# ProDoc_PT2470.net
KiCad netlist of a schematic drawn in EasyEDA Pro
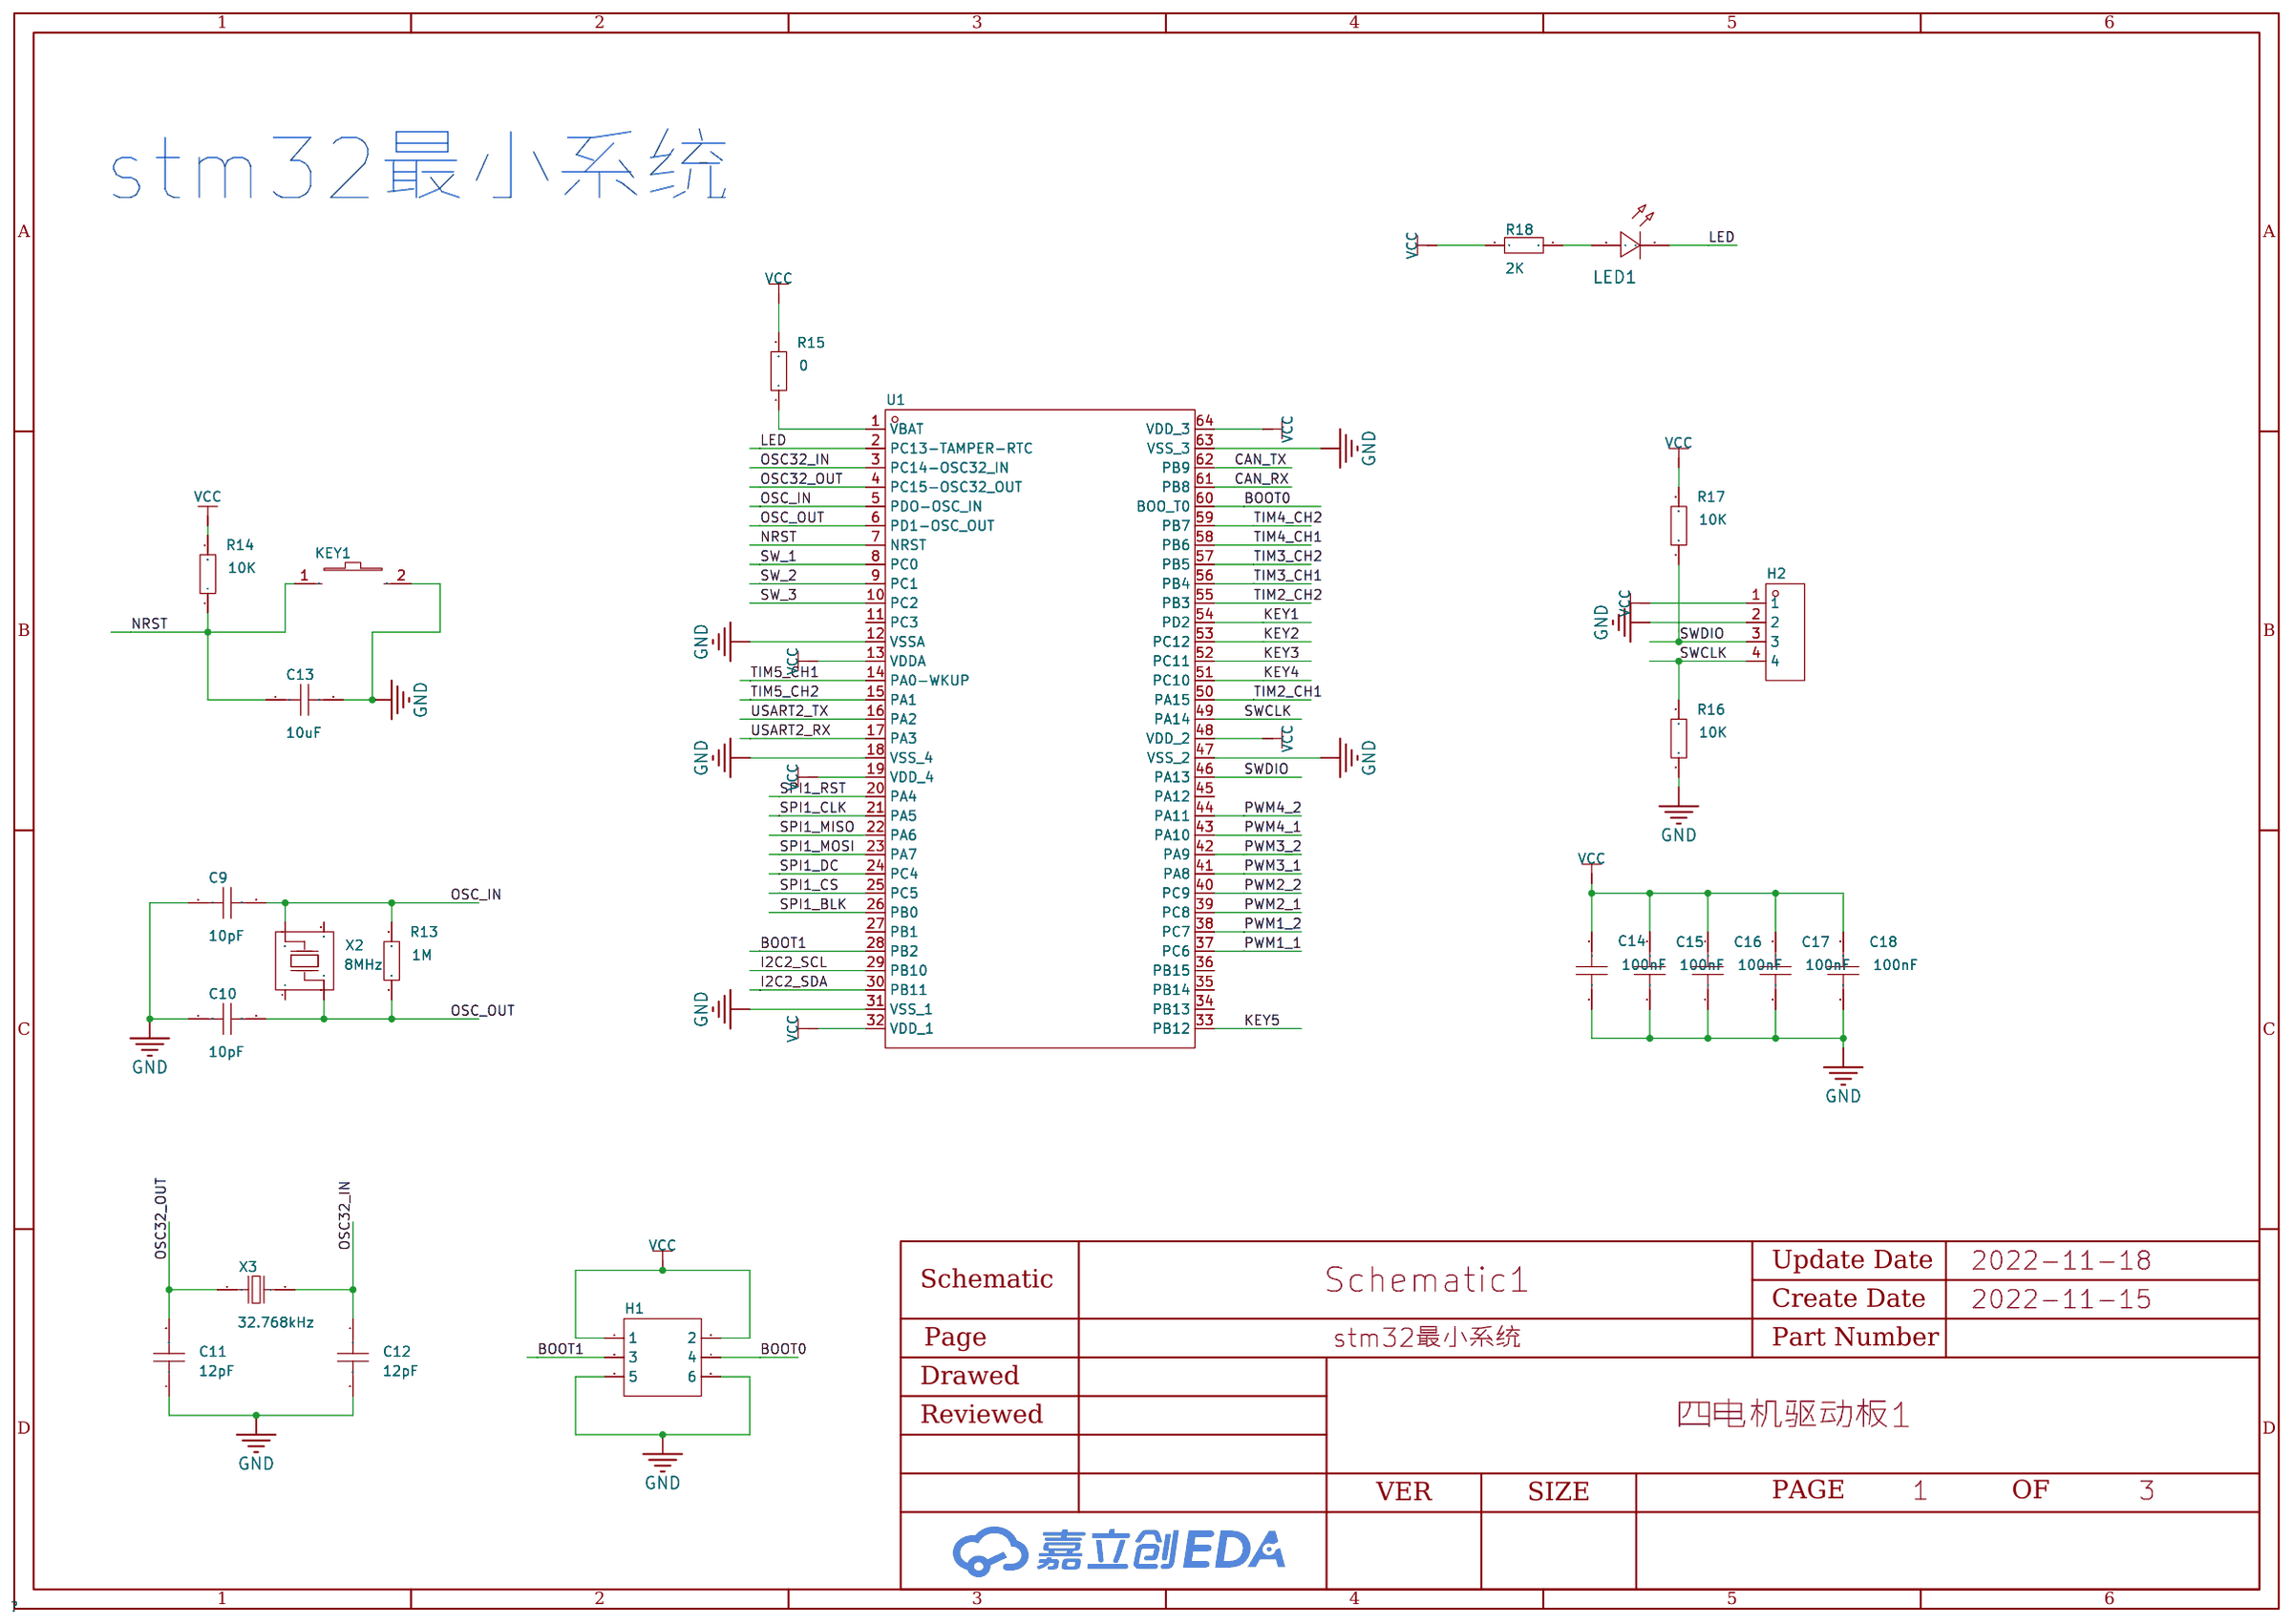
[diagram p0: stm32最小系统]
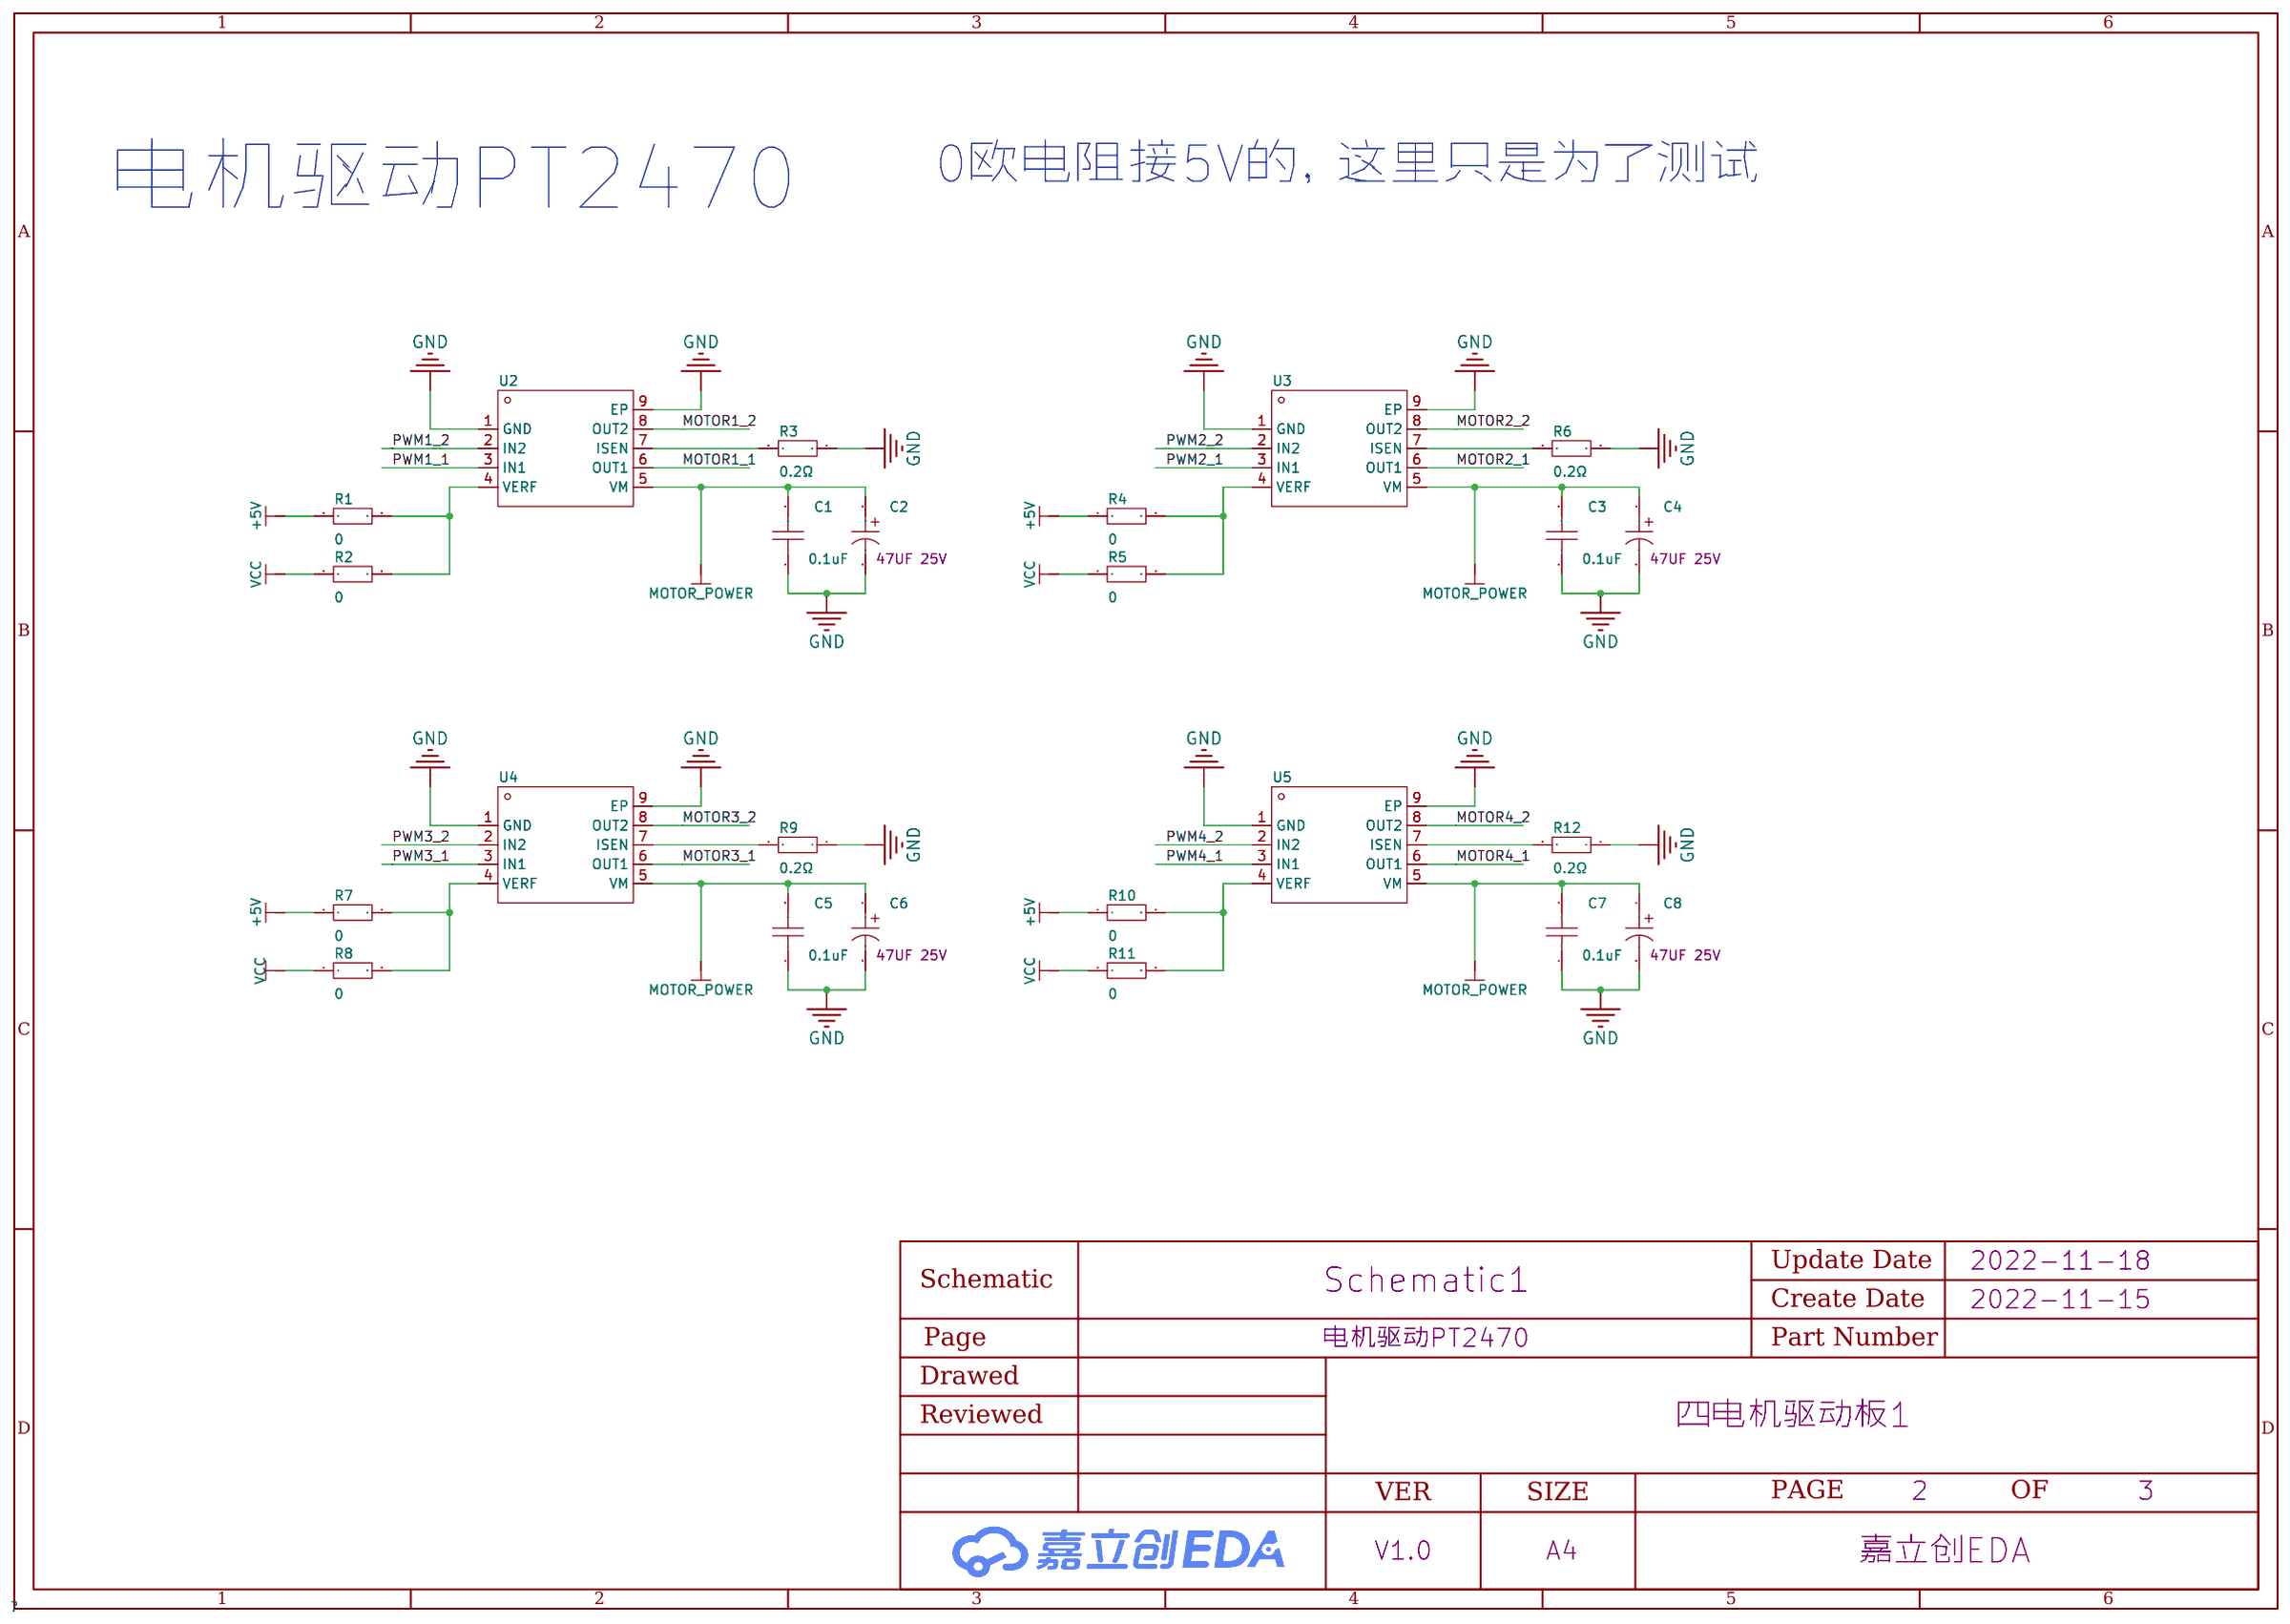
[diagram p1: 电机驱动PT2470]
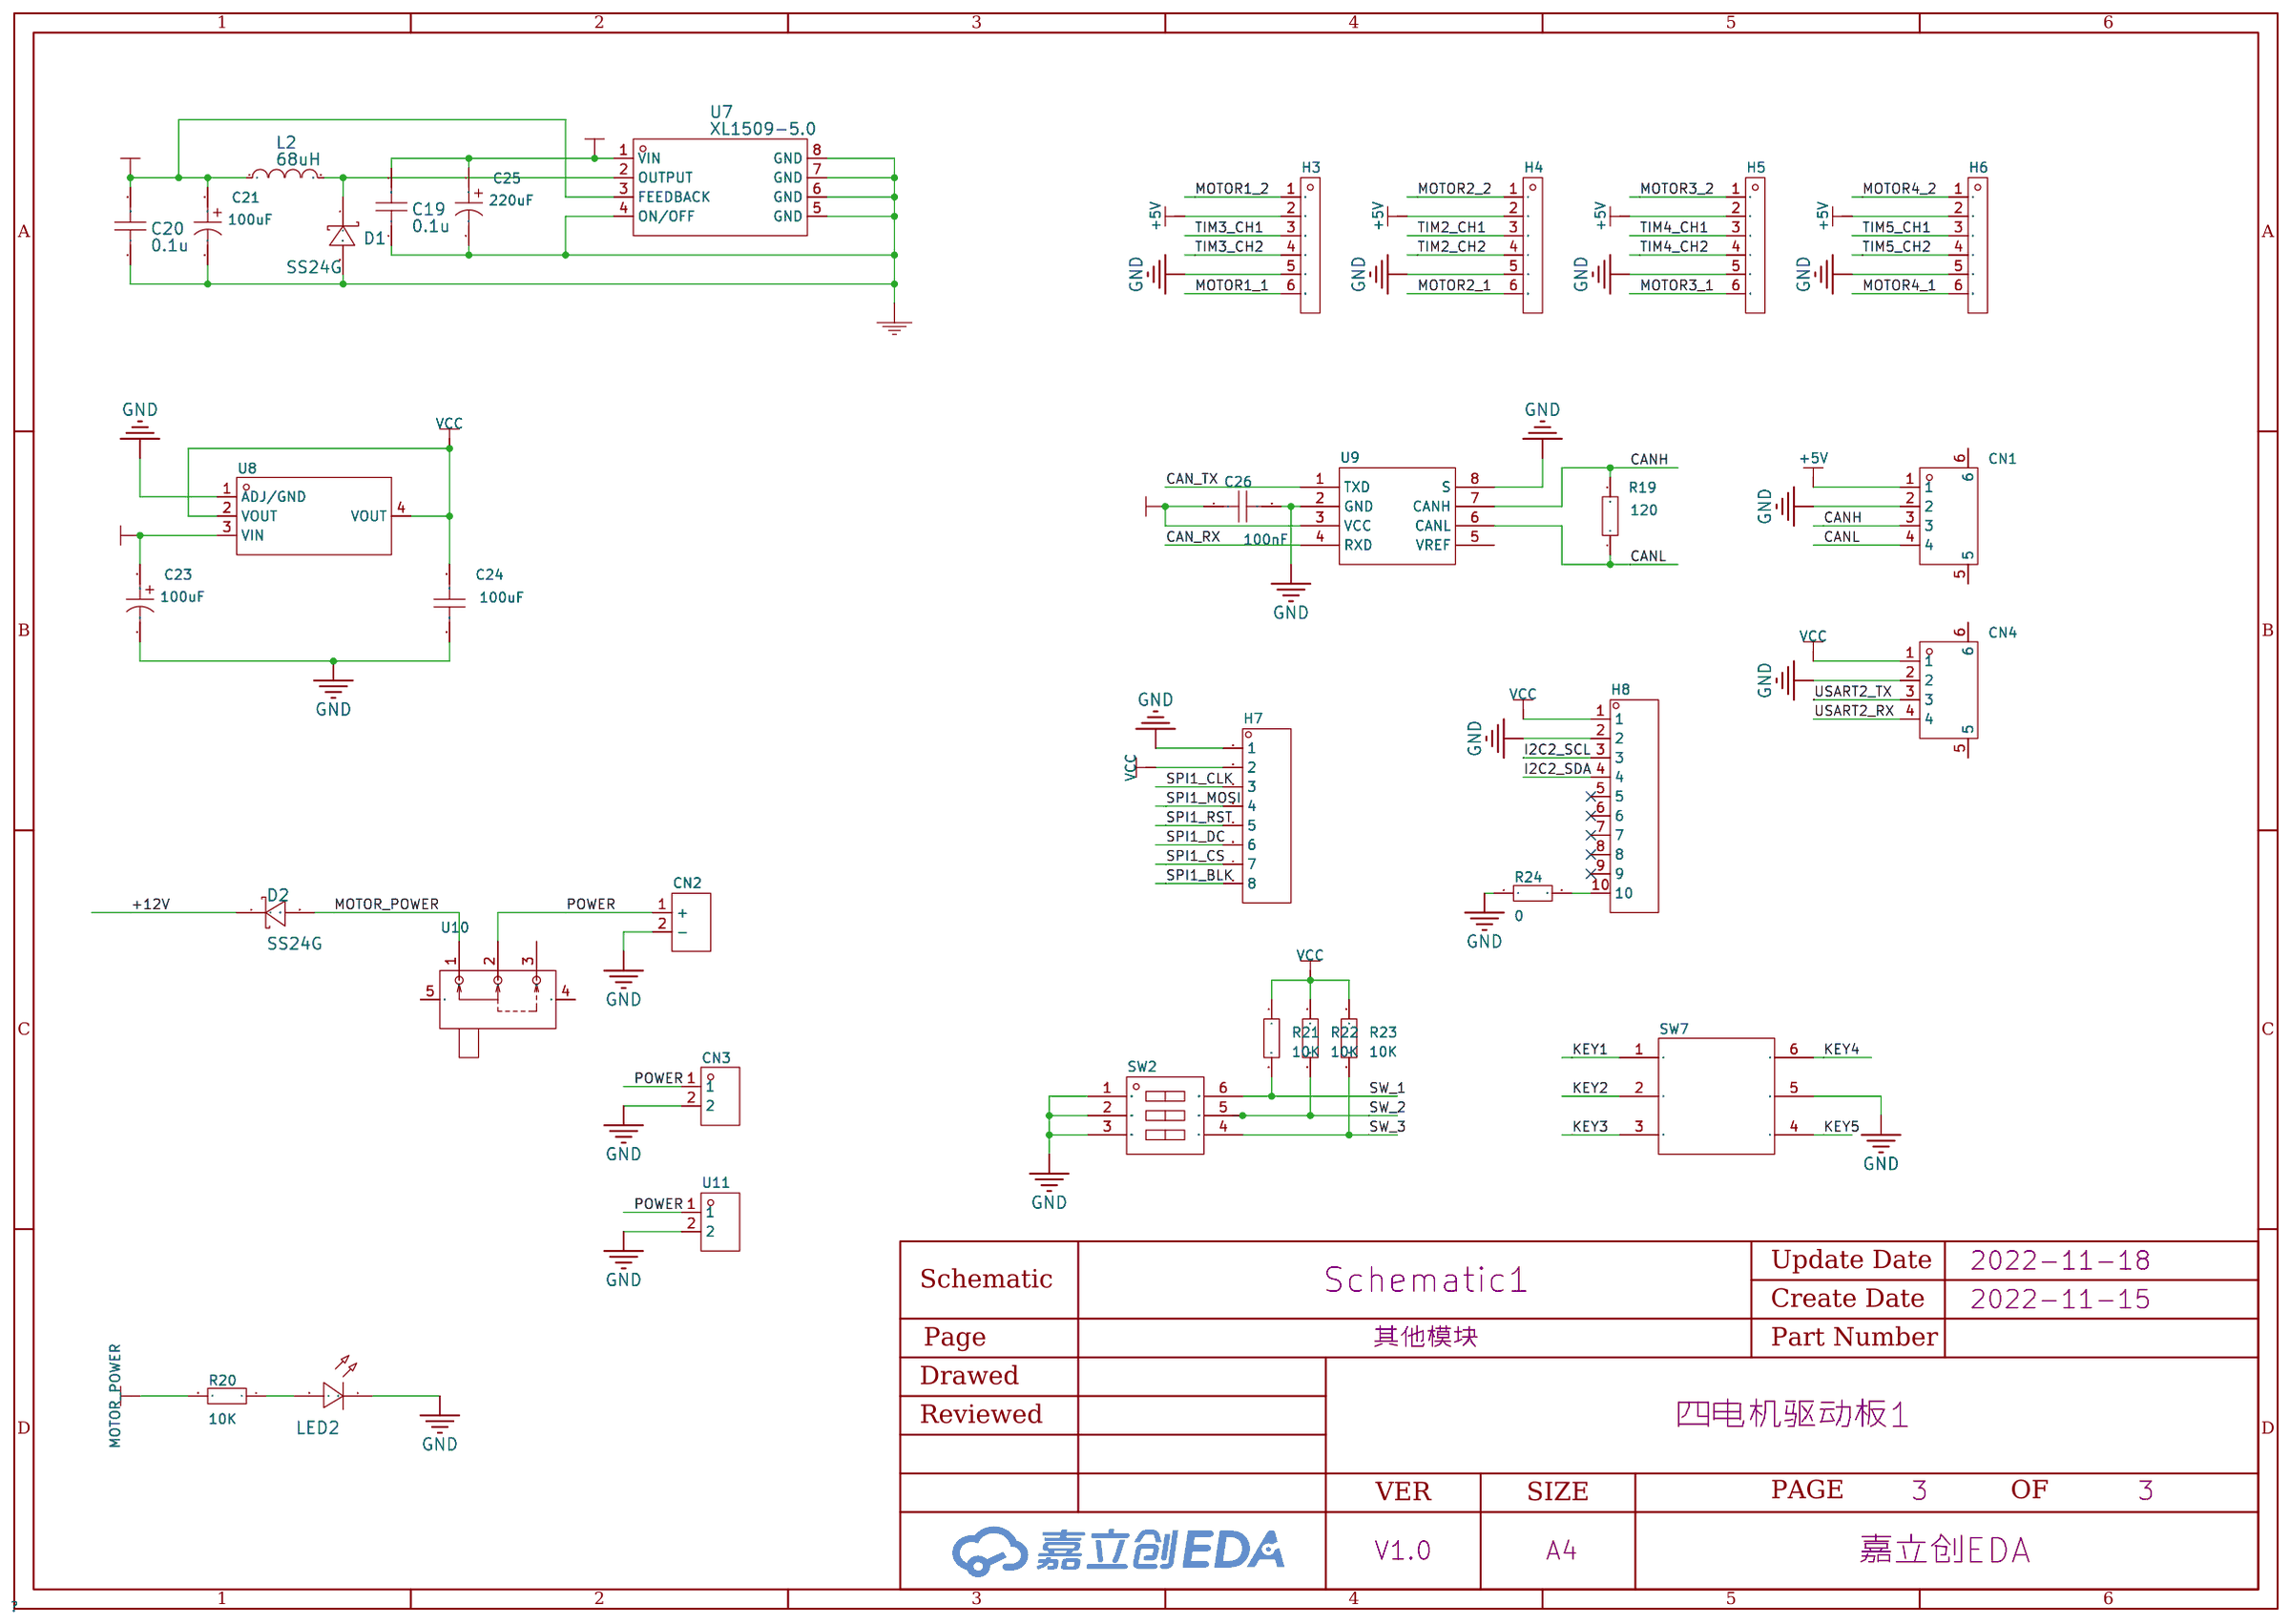
[diagram p2: 其他模块]

(export (version "E")
  (design (tool "Eeschema 10.0.6"))
  (components
    (comp (ref "C9")
      (value "10pF")
      (footprint "easyedapro:C0603")
      (libsource (lib "easyedapro") (part "C1210X7R475K630NT"))
    )
    (comp (ref "C10")
      (value "10pF")
      (footprint "easyedapro:C0603")
      (libsource (lib "easyedapro") (part "C1210X7R475K630NT"))
    )
    (comp (ref "C11")
      (value "12pF")
      (footprint "easyedapro:C0603")
      (libsource (lib "easyedapro") (part "C1210X7R475K630NT"))
    )
    (comp (ref "C12")
      (value "12pF")
      (footprint "easyedapro:C0603")
      (libsource (lib "easyedapro") (part "C1210X7R475K630NT"))
    )
    (comp (ref "C13")
      (value "10uF")
      (footprint "easyedapro:C0603")
      (fields
        (field (name "Manufacturer Part") "CC0603KRX7R9BB104")
        (field (name "Manufacturer") "YAGEO(国巨)")
        (field (name "Tolerance") "±10%")
      )
      (libsource (lib "easyedapro") (part "C1210X7R475K630NT"))
    )
    (comp (ref "C14")
      (value "100nF")
      (footprint "easyedapro:C0603")
      (libsource (lib "easyedapro") (part "C1210X7R475K630NT"))
    )
    (comp (ref "C15")
      (value "100nF")
      (footprint "easyedapro:C0603")
      (libsource (lib "easyedapro") (part "C1210X7R475K630NT"))
    )
    (comp (ref "C16")
      (value "100nF")
      (footprint "easyedapro:C0603")
      (libsource (lib "easyedapro") (part "C1210X7R475K630NT"))
    )
    (comp (ref "C17")
      (value "100nF")
      (footprint "easyedapro:C0603")
      (libsource (lib "easyedapro") (part "C1210X7R475K630NT"))
    )
    (comp (ref "C18")
      (value "100nF")
      (footprint "easyedapro:C0603")
      (libsource (lib "easyedapro") (part "C1210X7R475K630NT"))
    )
    (comp (ref "H1")
      (value "~")
      (footprint "easyedapro:HDR-TH_6P-P2.54-V-F-R2-C3-S2.54")
      (libsource (lib "easyedapro") (part "HDR-F-2.54_2x3"))
    )
    (comp (ref "H2")
      (value "~")
      (footprint "easyedapro:HDR-TH_4P-P2.54-V-M")
      (libsource (lib "easyedapro") (part "PZ254V-11-04P"))
    )
    (comp (ref "KEY1")
      (value "轻触开关3x4x2")
      (footprint "easyedapro:SW-SMD_L4.0-W2.9-LS5.0")
      (description "触点电流:50mA;额定电压(DC):12V;电路结构:单刀单掷;安装方式:立贴;按钮形状:圆形按钮;带灯:-;开关长度:4mm;开关宽度:3mm;开关高度:2mm;")
      (fields (field (name "Manufacturer") "国产"))
      (libsource (lib "easyedapro") (part "Switch3x4x2"))
    )
    (comp (ref "LED1")
      (value "~")
      (footprint "easyedapro:LED0805-RD_RED")
      (libsource (lib "easyedapro") (part "LED_R"))
    )
    (comp (ref "R13") (value "1M") (footprint "easyedapro:R0805") (libsource (lib "easyedapro") (part "电阻")))
    (comp (ref "R14") (value "10K") (footprint "easyedapro:R0805") (libsource (lib "easyedapro") (part "电阻")))
    (comp (ref "R15") (value "0") (footprint "easyedapro:R0805") (libsource (lib "easyedapro") (part "电阻")))
    (comp (ref "R16") (value "10K") (footprint "easyedapro:R0805") (libsource (lib "easyedapro") (part "电阻")))
    (comp (ref "R17") (value "10K") (footprint "easyedapro:R0805") (libsource (lib "easyedapro") (part "电阻")))
    (comp (ref "R18") (value "2K") (footprint "easyedapro:R0805") (libsource (lib "easyedapro") (part "电阻")))
    (comp (ref "U1")
      (value "~")
      (footprint "easyedapro:LQFP-64_L10.0-W10.0-P0.50-LS12.0-BL")
      (description "主频（MAX):72MHz;工作电压:2V ~ 3.6V;")
      (fields (field (name "Manufacturer Part") "STM32F103RCT6") (field (name "Manufacturer") "ST(意法半导体)"))
      (libsource (lib "easyedapro") (part "STM32F103RCT6"))
    )
    (comp (ref "X2")
      (value "8MHz")
      (footprint "easyedapro:OSC-SMD_4P-L3.2-W2.5-BL")
      (description "晶振类型:SMD 谐振器;频率:8MHz;频率公差:±10ppm;频率稳定度:±15ppm;负载电容:10pF;等效串联电阻(ESR):250Ω;工作温度:-;")
      (fields (field (name "Manufacturer Part") "TAXM8M4RDBCCT2T") (field (name "Manufacturer") "TAE(雅晶鑫)"))
      (libsource (lib "easyedapro") (part "TAXM8M4RDBCCT2T"))
    )
    (comp (ref "X3")
      (value "32.768kHz")
      (footprint "easyedapro:FC-135R_L3.2-W1.5")
      (description "晶振类型:贴片无源晶振;频率:32.768kHz;频率公差:±20ppm;负载电容:12.5pF;等效串联电阻(ESR):70kΩ;工作温度:-40~+85;")
      (fields (field (name "Manufacturer Part") "Q13FC1350000400") (field (name "Manufacturer") "EPSON(爱普生)"))
      (libsource (lib "easyedapro") (part "Q13FC1350000400"))
    )
    (comp (ref "C1")
      (value "0.1uF")
      (footprint "easyedapro:C0603")
      (libsource (lib "easyedapro") (part "C1210X7R475K630NT"))
    )
    (comp (ref "C2")
      (value "~")
      (footprint "easyedapro:CAP-SMD_BD6.3-L6.6-W6.6-LS7.6-FD")
      (description "工作寿命:2000hrs@105;")
      (fields
        (field (name "Manufacturer Part") "RVT47UF25V67RV0013")
        (field (name "Manufacturer") "KNSCHA(科尼盛)")
        (field (name "LCSC Part Name") "47UF 25V")
      )
      (libsource (lib "easyedapro") (part "RVT47UF25V67RV0013"))
    )
    (comp (ref "C3")
      (value "0.1uF")
      (footprint "easyedapro:C0603")
      (libsource (lib "easyedapro") (part "C1210X7R475K630NT"))
    )
    (comp (ref "C4")
      (value "~")
      (footprint "easyedapro:CAP-SMD_BD6.3-L6.6-W6.6-LS7.6-FD")
      (description "工作寿命:2000hrs@105;")
      (fields
        (field (name "Manufacturer Part") "RVT47UF25V67RV0013")
        (field (name "Manufacturer") "KNSCHA(科尼盛)")
        (field (name "LCSC Part Name") "47UF 25V")
      )
      (libsource (lib "easyedapro") (part "RVT47UF25V67RV0013"))
    )
    (comp (ref "C5")
      (value "0.1uF")
      (footprint "easyedapro:C0603")
      (libsource (lib "easyedapro") (part "C1210X7R475K630NT"))
    )
    (comp (ref "C6")
      (value "~")
      (footprint "easyedapro:CAP-SMD_BD6.3-L6.6-W6.6-LS7.6-FD")
      (description "工作寿命:2000hrs@105;")
      (fields
        (field (name "Manufacturer Part") "RVT47UF25V67RV0013")
        (field (name "Manufacturer") "KNSCHA(科尼盛)")
        (field (name "LCSC Part Name") "47UF 25V")
      )
      (libsource (lib "easyedapro") (part "RVT47UF25V67RV0013"))
    )
    (comp (ref "C7")
      (value "0.1uF")
      (footprint "easyedapro:C0603")
      (libsource (lib "easyedapro") (part "C1210X7R475K630NT"))
    )
    (comp (ref "C8")
      (value "~")
      (footprint "easyedapro:CAP-SMD_BD6.3-L6.6-W6.6-LS7.6-FD")
      (description "工作寿命:2000hrs@105;")
      (fields
        (field (name "Manufacturer Part") "RVT47UF25V67RV0013")
        (field (name "Manufacturer") "KNSCHA(科尼盛)")
        (field (name "LCSC Part Name") "47UF 25V")
      )
      (libsource (lib "easyedapro") (part "RVT47UF25V67RV0013"))
    )
    (comp (ref "R1") (value "0") (footprint "easyedapro:R0805") (libsource (lib "easyedapro") (part "电阻")))
    (comp (ref "R2") (value "0") (footprint "easyedapro:R0805") (libsource (lib "easyedapro") (part "电阻")))
    (comp (ref "R3") (value "0.2Ω") (footprint "easyedapro:R0805") (libsource (lib "easyedapro") (part "电阻")))
    (comp (ref "R4") (value "0") (footprint "easyedapro:R0805") (libsource (lib "easyedapro") (part "电阻")))
    (comp (ref "R5") (value "0") (footprint "easyedapro:R0805") (libsource (lib "easyedapro") (part "电阻")))
    (comp (ref "R6") (value "0.2Ω") (footprint "easyedapro:R0805") (libsource (lib "easyedapro") (part "电阻")))
    (comp (ref "R7") (value "0") (footprint "easyedapro:R0805") (libsource (lib "easyedapro") (part "电阻")))
    (comp (ref "R8") (value "0") (footprint "easyedapro:R0805") (libsource (lib "easyedapro") (part "电阻")))
    (comp (ref "R9") (value "0.2Ω") (footprint "easyedapro:R0805") (libsource (lib "easyedapro") (part "电阻")))
    (comp (ref "R10") (value "0") (footprint "easyedapro:R0805") (libsource (lib "easyedapro") (part "电阻")))
    (comp (ref "R11") (value "0") (footprint "easyedapro:R0805") (libsource (lib "easyedapro") (part "电阻")))
    (comp (ref "R12")
      (value "0.2Ω")
      (footprint "easyedapro:R0805")
      (libsource (lib "easyedapro") (part "电阻"))
    )
    (comp (ref "U2")
      (value "~")
      (footprint "easyedapro:HSOP-8_L5.0-W4.0-P1.27-LS6.2-BL-EP")
      (fields (field (name "Manufacturer Part") "PT2470") (field (name "Manufacturer") "PTC(台湾普诚)"))
      (libsource (lib "easyedapro") (part "PT2470"))
    )
    (comp (ref "U3")
      (value "~")
      (footprint "easyedapro:HSOP-8_L5.0-W4.0-P1.27-LS6.2-BL-EP")
      (fields (field (name "Manufacturer Part") "PT2470") (field (name "Manufacturer") "PTC(台湾普诚)"))
      (libsource (lib "easyedapro") (part "PT2470"))
    )
    (comp (ref "U4")
      (value "~")
      (footprint "easyedapro:HSOP-8_L5.0-W4.0-P1.27-LS6.2-BL-EP")
      (fields (field (name "Manufacturer Part") "PT2470") (field (name "Manufacturer") "PTC(台湾普诚)"))
      (libsource (lib "easyedapro") (part "PT2470"))
    )
    (comp (ref "U5")
      (value "~")
      (footprint "easyedapro:HSOP-8_L5.0-W4.0-P1.27-LS6.2-BL-EP")
      (fields (field (name "Manufacturer Part") "PT2470") (field (name "Manufacturer") "PTC(台湾普诚)"))
      (libsource (lib "easyedapro") (part "PT2470"))
    )
    (comp (ref "C19")
      (value "0.1u")
      (footprint "easyedapro:C0603")
      (libsource (lib "easyedapro") (part "0.1u"))
    )
    (comp (ref "C20")
      (value "0.1u")
      (footprint "easyedapro:C0603")
      (libsource (lib "easyedapro") (part "0.1u"))
    )
    (comp (ref "C21")
      (value "100uF")
      (footprint "easyedapro:CAP-SMD_BD6.3-L6.6-W6.6-LS7.3-FD")
      (description "容值:100uF;精度:±20%;额定电压:16V;电容体直径:6.3mm;电容体长度:7.7mm;纹波电流:85mA@120Hz;工作寿命:2000hrs@105;工作温度:-55~+105;")
      (fields
        (field (name "Manufacturer Part") "XT100UF16V90RV0074")
        (field (name "Manufacturer") "KNSCHA(科尼盛)")
      )
      (libsource (lib "easyedapro") (part "XT100UF16V90RV0074"))
    )
    (comp (ref "C23")
      (value "100uF")
      (footprint "easyedapro:CAP-SMD_BD6.3-L6.6-W6.6-LS7.3-FD")
      (description "容值:100uF;精度:±20%;额定电压:16V;电容体直径:6.3mm;电容体长度:7.7mm;纹波电流:85mA@120Hz;工作寿命:2000hrs@105;工作温度:-55~+105;")
      (fields
        (field (name "Manufacturer Part") "XT100UF16V90RV0074")
        (field (name "Manufacturer") "KNSCHA(科尼盛)")
      )
      (libsource (lib "easyedapro") (part "XT100UF16V90RV0074"))
    )
    (comp (ref "C24")
      (value "100uF")
      (footprint "easyedapro:C0603")
      (libsource (lib "easyedapro") (part "C1210X7R475K630NT"))
    )
    (comp (ref "C25")
      (value "220uF")
      (footprint "easyedapro:CAP-SMD_BD6.3-L6.6-W6.6-LS7.3-FD")
      (description "容值:220uF;额定电压:25V;电容体直径:-;电容体长度:-;纹波电流:-;等效串联电阻:-;工作寿命:-;")
      (fields
        (field (name "Manufacturer Part") "XT220UF25V90RV0075")
        (field (name "Manufacturer") "KNSCHA(科尼盛)")
      )
      (libsource (lib "easyedapro") (part "XT220UF25V90RV0075"))
    )
    (comp (ref "C26")
      (value "100nF")
      (footprint "easyedapro:C0603")
      (libsource (lib "easyedapro") (part "C1210X7R475K630NT"))
    )
    (comp (ref "CN1")
      (value "PH-4P卧贴")
      (footprint "easyedapro:CONN-SMD_PH2.0-4PWB")
      (description "参考系列:PH;间距:2mm;插针结构:1x4P;排数:1;每排PIN数:4;行距:-;安装方式:-;触头材质:-;")
      (fields (field (name "Manufacturer") "BOOMELE(博穆精密)"))
      (libsource (lib "easyedapro") (part "PH2.0-4PWB卧式"))
    )
    (comp (ref "CN2")
      (value "XT30UPB-F")
      (footprint "easyedapro:CONN-TH_XT30UPB-F")
      (description "模型插头连接器")
      (fields (field (name "Manufacturer") "AMASS(艾迈斯)"))
      (libsource (lib "easyedapro") (part "XT30UPB-F"))
    )
    (comp (ref "CN3")
      (value "XT30U-M")
      (footprint "easyedapro:CONN-TH_XT30U-M")
      (description "模型插头轻量版锂电池插头")
      (fields (field (name "Manufacturer") "AMASS(艾迈斯)"))
      (libsource (lib "easyedapro") (part "XT30U-M"))
    )
    (comp (ref "CN4")
      (value "PH-4P卧贴")
      (footprint "easyedapro:CONN-SMD_PH2.0-4PWB")
      (description "参考系列:PH;间距:2mm;插针结构:1x4P;排数:1;每排PIN数:4;行距:-;安装方式:-;触头材质:-;")
      (fields (field (name "Manufacturer") "BOOMELE(博穆精密)"))
      (libsource (lib "easyedapro") (part "PH2.0-4PWB卧式"))
    )
    (comp (ref "D1")
      (value "SS24G")
      (footprint "easyedapro:SMA_L4.4-W2.8-LS5.4-RD")
      (fields (field (name "Manufacturer") "SK"))
      (libsource (lib "easyedapro") (part "SS24G"))
    )
    (comp (ref "D2")
      (value "SS24G")
      (footprint "easyedapro:SMA_L4.4-W2.8-LS5.4-RD")
      (fields (field (name "Manufacturer") "SK"))
      (libsource (lib "easyedapro") (part "SS24G"))
    )
    (comp (ref "H3")
      (value "~")
      (footprint "easyedapro:CONN-TH_XH-6AW")
      (description "参考系列:XH;间距:2.5mm;插针结构:1x6P;排数:1;每排PIN数:6;行距:-;安装方式:-;触头材质:-;")
      (fields (field (name "Manufacturer Part") "XH-6AW") (field (name "Manufacturer") "BOOMELE(博穆精密)"))
      (libsource (lib "easyedapro") (part "6P接插件"))
    )
    (comp (ref "H4")
      (value "~")
      (footprint "easyedapro:CONN-TH_XH-6AW")
      (description "参考系列:XH;间距:2.5mm;插针结构:1x6P;排数:1;每排PIN数:6;行距:-;安装方式:-;触头材质:-;")
      (fields (field (name "Manufacturer Part") "XH-6AW") (field (name "Manufacturer") "BOOMELE(博穆精密)"))
      (libsource (lib "easyedapro") (part "6P接插件"))
    )
    (comp (ref "H5")
      (value "~")
      (footprint "easyedapro:CONN-TH_XH-6AW")
      (description "参考系列:XH;间距:2.5mm;插针结构:1x6P;排数:1;每排PIN数:6;行距:-;安装方式:-;触头材质:-;")
      (fields (field (name "Manufacturer Part") "XH-6AW") (field (name "Manufacturer") "BOOMELE(博穆精密)"))
      (libsource (lib "easyedapro") (part "6P接插件"))
    )
    (comp (ref "H6")
      (value "~")
      (footprint "easyedapro:CONN-TH_XH-6AW")
      (description "参考系列:XH;间距:2.5mm;插针结构:1x6P;排数:1;每排PIN数:6;行距:-;安装方式:-;触头材质:-;")
      (fields (field (name "Manufacturer Part") "XH-6AW") (field (name "Manufacturer") "BOOMELE(博穆精密)"))
      (libsource (lib "easyedapro") (part "6P接插件"))
    )
    (comp (ref "H7")
      (value "~")
      (footprint "easyedapro:HDR-TH_8P-P2.54-V-M")
      (libsource (lib "easyedapro") (part "Header-Male-2.54_1x8"))
    )
    (comp (ref "H8")
      (value "~")
      (footprint "easyedapro:HDR-TH_10P-P2.54-V-M-1")
      (libsource (lib "easyedapro") (part "Header-Male-2.54_1x10"))
    )
    (comp (ref "L2")
      (value "68uH")
      (footprint "easyedapro:IND-SMD_L5.8-W5.2_CD54T125NP-100MC")
      (fields (field (name "Manufacturer Part") "CD54T125NP-100MC") (field (name "Manufacturer") "Sumida"))
      (libsource (lib "easyedapro") (part "68uH"))
    )
    (comp (ref "LED2")
      (value "~")
      (footprint "easyedapro:LED0805-RD_RED")
      (libsource (lib "easyedapro") (part "LED_R"))
    )
    (comp (ref "R19") (value "120") (footprint "easyedapro:R0805") (libsource (lib "easyedapro") (part "电阻")))
    (comp (ref "R20") (value "10K") (footprint "easyedapro:R0805") (libsource (lib "easyedapro") (part "电阻")))
    (comp (ref "R21") (value "10K") (footprint "easyedapro:R0805") (libsource (lib "easyedapro") (part "电阻")))
    (comp (ref "R22") (value "10K") (footprint "easyedapro:R0805") (libsource (lib "easyedapro") (part "电阻")))
    (comp (ref "R23") (value "10K") (footprint "easyedapro:R0805") (libsource (lib "easyedapro") (part "电阻")))
    (comp (ref "R24") (value "0") (footprint "easyedapro:R0805") (libsource (lib "easyedapro") (part "电阻")))
    (comp (ref "SW2")
      (value "TO-03")
      (footprint "easyedapro:SW-SMD_6P-L7.6-W6.3-P2.54-LS9.8")
      (description "拨码开关贴片黑色03P-3PIN间距2.54mm立式贴片正拨平拨3位SMD")
      (fields (field (name "Manufacturer") "Yuandi(台湾元迪)"))
      (libsource (lib "easyedapro") (part "TO-03"))
    )
    (comp (ref "SW7")
      (value "7*7*5-6P-L WX")
      (footprint "easyedapro:SW-SMD_6P-L7.0-W7.0-P1.40-LS7.4")
      (fields (field (name "Manufacturer") "SHOU HAN(首韩)"))
      (libsource (lib "easyedapro") (part "7*7*5-6P-L WX"))
    )
    (comp (ref "U7")
      (value "XL1509-5.0")
      (footprint "easyedapro:SOIC-8_L5.0-W4.0-P1.27-LS6.0-BL")
      (fields (field (name "Manufacturer") "UMW(友台半导体)"))
      (libsource (lib "easyedapro") (part "XL1509-5.0"))
    )
    (comp (ref "U8")
      (value "AMS1117-3.3")
      (footprint "easyedapro:SOT-223_L6.5-W3.5-P2.30-LS7.0-BR")
      (fields (field (name "Manufacturer") "PUOLOP(迪浦)"))
      (libsource (lib "easyedapro") (part "AMS1117-3.3_C351785"))
    )
    (comp (ref "U9")
      (value "TJA1050T/CM,118")
      (footprint "easyedapro:SOIC-8_L5.0-W4.0-P1.27-LS6.0-BL")
      (description "类型:收发器;协议类别:CAN总线;")
      (fields (field (name "Manufacturer") "NXP(恩智浦)"))
      (libsource (lib "easyedapro") (part "TJA1050T/CM,118"))
    )
    (comp (ref "U10")
      (value "SS-12F23-G4")
      (footprint "easyedapro:SW-TH_SS-12F23-G040")
      (description "电路结构:单刀双掷;安装方式:卧插;开关颜色:黑色;滑钮形状:矩形柱状;引脚样式:PC引脚;开关长度:13mm;开关宽度:5.8mm;开关高度:9mm;")
      (fields (field (name "Manufacturer") "DEALON(德艺隆)"))
      (libsource (lib "easyedapro") (part "SS-12F23-G4"))
    )
    (comp (ref "U11")
      (value "KF127-5.08-2P")
      (footprint "easyedapro:CONN-TH_P5.08_KF127-5.08-2P")
      (fields (field (name "Manufacturer") "KEFA(科发)"))
      (libsource (lib "easyedapro") (part "KF127-5.08-2P"))
    )
  )
  (nets
    (net (code "1") (name "+5V") (class "Default")
      (node (ref "C20") (pin "2") (pinfunction "2_2") (pintype "input"))
      (node (ref "C21") (pin "1") (pinfunction "1_1") (pintype "input"))
      (node (ref "C23") (pin "1") (pinfunction "1_1") (pintype "input"))
      (node (ref "C26") (pin "1") (pinfunction "1_1") (pintype "input"))
      (node (ref "CN1") (pin "1") (pinfunction "1_1") (pintype "input"))
      (node (ref "H3") (pin "2") (pinfunction "2_2") (pintype "input"))
      (node (ref "H4") (pin "2") (pinfunction "2_2") (pintype "input"))
      (node (ref "H5") (pin "2") (pinfunction "2_2") (pintype "input"))
      (node (ref "H6") (pin "2") (pinfunction "2_2") (pintype "input"))
      (node (ref "L2") (pin "1") (pinfunction "1_1") (pintype "input"))
      (node (ref "R1") (pin "1") (pinfunction "1_1") (pintype "input"))
      (node (ref "R10") (pin "1") (pinfunction "1_1") (pintype "input"))
      (node (ref "R4") (pin "1") (pinfunction "1_1") (pintype "input"))
      (node (ref "R7") (pin "1") (pinfunction "1_1") (pintype "input"))
      (node (ref "U7") (pin "3") (pinfunction "FEEDBACK_3") (pintype "input"))
      (node (ref "U8") (pin "3") (pinfunction "VIN_3") (pintype "input"))
      (node (ref "U9") (pin "3") (pinfunction "VCC_3") (pintype "input"))
    )
    (net (code "2") (name "+12V") (class "Default")
      (node (ref "C19") (pin "2") (pinfunction "2_2") (pintype "input"))
      (node (ref "C25") (pin "1") (pinfunction "1_1") (pintype "input"))
      (node (ref "D2") (pin "1") (pinfunction "1_1") (pintype "input"))
      (node (ref "U7") (pin "1") (pinfunction "VIN_1") (pintype "input"))
    )
    (net (code "3") (name "BOOT0") (class "Default")
      (node (ref "H1") (pin "4") (pinfunction "4_4") (pintype "input"))
      (node (ref "U1") (pin "60") (pinfunction "BOO_T0_60") (pintype "input"))
    )
    (net (code "4") (name "BOOT1") (class "Default")
      (node (ref "H1") (pin "3") (pinfunction "3_3") (pintype "input"))
      (node (ref "U1") (pin "28") (pinfunction "PB2_28") (pintype "input"))
    )
    (net (code "5") (name "CANH") (class "Default")
      (node (ref "CN1") (pin "3") (pinfunction "3_3") (pintype "input"))
      (node (ref "R19") (pin "2") (pinfunction "2_2") (pintype "input"))
      (node (ref "U9") (pin "7") (pinfunction "CANH_7") (pintype "input"))
    )
    (net (code "6") (name "CANL") (class "Default")
      (node (ref "CN1") (pin "4") (pinfunction "4_4") (pintype "input"))
      (node (ref "R19") (pin "1") (pinfunction "1_1") (pintype "input"))
      (node (ref "U9") (pin "6") (pinfunction "CANL_6") (pintype "input"))
    )
    (net (code "7") (name "CAN_RX") (class "Default")
      (node (ref "U1") (pin "61") (pinfunction "PB8_61") (pintype "input"))
      (node (ref "U9") (pin "4") (pinfunction "RXD_4") (pintype "input"))
    )
    (net (code "8") (name "CAN_TX") (class "Default")
      (node (ref "U1") (pin "62") (pinfunction "PB9_62") (pintype "input"))
      (node (ref "U9") (pin "1") (pinfunction "TXD_1") (pintype "input"))
    )
    (net (code "9") (name "GND") (class "Default")
      (node (ref "C1") (pin "1") (pinfunction "1_1") (pintype "input"))
      (node (ref "C10") (pin "1") (pinfunction "1_1") (pintype "input"))
      (node (ref "C11") (pin "1") (pinfunction "1_1") (pintype "input"))
      (node (ref "C12") (pin "2") (pinfunction "2_2") (pintype "input"))
      (node (ref "C13") (pin "2") (pinfunction "2_2") (pintype "input"))
      (node (ref "C14") (pin "1") (pinfunction "1_1") (pintype "input"))
      (node (ref "C15") (pin "1") (pinfunction "1_1") (pintype "input"))
      (node (ref "C16") (pin "1") (pinfunction "1_1") (pintype "input"))
      (node (ref "C17") (pin "1") (pinfunction "1_1") (pintype "input"))
      (node (ref "C18") (pin "1") (pinfunction "1_1") (pintype "input"))
      (node (ref "C19") (pin "1") (pinfunction "1_1") (pintype "input"))
      (node (ref "C2") (pin "2") (pinfunction "2_2") (pintype "input"))
      (node (ref "C20") (pin "1") (pinfunction "1_1") (pintype "input"))
      (node (ref "C21") (pin "2") (pinfunction "2_2") (pintype "input"))
      (node (ref "C23") (pin "2") (pinfunction "2_2") (pintype "input"))
      (node (ref "C24") (pin "1") (pinfunction "1_1") (pintype "input"))
      (node (ref "C25") (pin "2") (pinfunction "2_2") (pintype "input"))
      (node (ref "C26") (pin "2") (pinfunction "2_2") (pintype "input"))
      (node (ref "C3") (pin "1") (pinfunction "1_1") (pintype "input"))
      (node (ref "C4") (pin "2") (pinfunction "2_2") (pintype "input"))
      (node (ref "C5") (pin "1") (pinfunction "1_1") (pintype "input"))
      (node (ref "C6") (pin "2") (pinfunction "2_2") (pintype "input"))
      (node (ref "C7") (pin "1") (pinfunction "1_1") (pintype "input"))
      (node (ref "C8") (pin "2") (pinfunction "2_2") (pintype "input"))
      (node (ref "C9") (pin "1") (pinfunction "1_1") (pintype "input"))
      (node (ref "CN1") (pin "2") (pinfunction "2_2") (pintype "input"))
      (node (ref "CN2") (pin "2") (pinfunction "-_2") (pintype "input"))
      (node (ref "CN3") (pin "2") (pinfunction "2_2") (pintype "input"))
      (node (ref "CN4") (pin "2") (pinfunction "2_2") (pintype "input"))
      (node (ref "D1") (pin "2") (pinfunction "2_2") (pintype "input"))
      (node (ref "H1") (pin "5") (pinfunction "5_5") (pintype "input"))
      (node (ref "H1") (pin "6") (pinfunction "6_6") (pintype "input"))
      (node (ref "H2") (pin "2") (pinfunction "2_2") (pintype "input"))
      (node (ref "H3") (pin "5") (pinfunction "5_5") (pintype "input"))
      (node (ref "H4") (pin "5") (pinfunction "5_5") (pintype "input"))
      (node (ref "H5") (pin "5") (pinfunction "5_5") (pintype "input"))
      (node (ref "H6") (pin "5") (pinfunction "5_5") (pintype "input"))
      (node (ref "H7") (pin "1") (pinfunction "1_1") (pintype "input"))
      (node (ref "H8") (pin "2") (pinfunction "2_2") (pintype "input"))
      (node (ref "KEY1") (pin "2") (pinfunction "2_2") (pintype "input"))
      (node (ref "LED2") (pin "1") (pinfunction "C_1") (pintype "input"))
      (node (ref "R12") (pin "1") (pinfunction "1_1") (pintype "input"))
      (node (ref "R16") (pin "1") (pinfunction "1_1") (pintype "input"))
      (node (ref "R24") (pin "1") (pinfunction "1_1") (pintype "input"))
      (node (ref "R3") (pin "1") (pinfunction "1_1") (pintype "input"))
      (node (ref "R6") (pin "1") (pinfunction "1_1") (pintype "input"))
      (node (ref "R9") (pin "1") (pinfunction "1_1") (pintype "input"))
      (node (ref "SW2") (pin "1") (pinfunction "PIN1_1") (pintype "input"))
      (node (ref "SW2") (pin "2") (pinfunction "PIN2_2") (pintype "input"))
      (node (ref "SW2") (pin "3") (pinfunction "PIN3_3") (pintype "input"))
      (node (ref "SW7") (pin "5") (pinfunction "5_5") (pintype "input"))
      (node (ref "U1") (pin "12") (pinfunction "VSSA_12") (pintype "input"))
      (node (ref "U1") (pin "18") (pinfunction "VSS_4_18") (pintype "input"))
      (node (ref "U1") (pin "31") (pinfunction "VSS_1_31") (pintype "input"))
      (node (ref "U1") (pin "47") (pinfunction "VSS_2_47") (pintype "input"))
      (node (ref "U1") (pin "63") (pinfunction "VSS_3_63") (pintype "input"))
      (node (ref "U11") (pin "2") (pinfunction "2_2") (pintype "input"))
      (node (ref "U2") (pin "1") (pinfunction "GND_1") (pintype "input"))
      (node (ref "U2") (pin "9") (pinfunction "EP_9") (pintype "input"))
      (node (ref "U3") (pin "1") (pinfunction "GND_1") (pintype "input"))
      (node (ref "U3") (pin "9") (pinfunction "EP_9") (pintype "input"))
      (node (ref "U4") (pin "1") (pinfunction "GND_1") (pintype "input"))
      (node (ref "U4") (pin "9") (pinfunction "EP_9") (pintype "input"))
      (node (ref "U5") (pin "1") (pinfunction "GND_1") (pintype "input"))
      (node (ref "U5") (pin "9") (pinfunction "EP_9") (pintype "input"))
      (node (ref "U7") (pin "4") (pinfunction "ON/OFF_4") (pintype "input"))
      (node (ref "U7") (pin "5") (pinfunction "GND_5") (pintype "input"))
      (node (ref "U7") (pin "6") (pinfunction "GND_6") (pintype "input"))
      (node (ref "U7") (pin "7") (pinfunction "GND_7") (pintype "input"))
      (node (ref "U7") (pin "8") (pinfunction "GND_8") (pintype "input"))
      (node (ref "U8") (pin "1") (pinfunction "ADJ/GND_1") (pintype "input"))
      (node (ref "U9") (pin "2") (pinfunction "GND_2") (pintype "input"))
      (node (ref "U9") (pin "8") (pinfunction "S_8") (pintype "input"))
    )
    (net (code "10") (name "I2C2_SCL") (class "Default")
      (node (ref "H8") (pin "3") (pinfunction "3_3") (pintype "input"))
      (node (ref "U1") (pin "29") (pinfunction "PB10_29") (pintype "input"))
    )
    (net (code "11") (name "I2C2_SDA") (class "Default")
      (node (ref "H8") (pin "4") (pinfunction "4_4") (pintype "input"))
      (node (ref "U1") (pin "30") (pinfunction "PB11_30") (pintype "input"))
    )
    (net (code "12") (name "KEY1") (class "Default")
      (node (ref "SW7") (pin "1") (pinfunction "1_1") (pintype "input"))
      (node (ref "U1") (pin "54") (pinfunction "PD2_54") (pintype "input"))
    )
    (net (code "13") (name "KEY2") (class "Default")
      (node (ref "SW7") (pin "2") (pinfunction "2_2") (pintype "input"))
      (node (ref "U1") (pin "53") (pinfunction "PC12_53") (pintype "input"))
    )
    (net (code "14") (name "KEY3") (class "Default")
      (node (ref "SW7") (pin "3") (pinfunction "3_3") (pintype "input"))
      (node (ref "U1") (pin "52") (pinfunction "PC11_52") (pintype "input"))
    )
    (net (code "15") (name "KEY4") (class "Default")
      (node (ref "SW7") (pin "6") (pinfunction "6_6") (pintype "input"))
      (node (ref "U1") (pin "51") (pinfunction "PC10_51") (pintype "input"))
    )
    (net (code "16") (name "KEY5") (class "Default")
      (node (ref "SW7") (pin "4") (pinfunction "4_4") (pintype "input"))
      (node (ref "U1") (pin "33") (pinfunction "PB12_33") (pintype "input"))
    )
    (net (code "17") (name "LED") (class "Default")
      (node (ref "LED1") (pin "1") (pinfunction "C_1") (pintype "input"))
      (node (ref "U1") (pin "2") (pinfunction "PC13-TAMPER-RTC_2") (pintype "input"))
    )
    (net (code "18") (name "MOTOR1_1") (class "Default")
      (node (ref "H3") (pin "6") (pinfunction "6_6") (pintype "input"))
      (node (ref "U2") (pin "6") (pinfunction "OUT1_6") (pintype "input"))
    )
    (net (code "19") (name "MOTOR1_2") (class "Default")
      (node (ref "H3") (pin "1") (pinfunction "1_1") (pintype "input"))
      (node (ref "U2") (pin "8") (pinfunction "OUT2_8") (pintype "input"))
    )
    (net (code "20") (name "MOTOR2_1") (class "Default")
      (node (ref "H4") (pin "6") (pinfunction "6_6") (pintype "input"))
      (node (ref "U3") (pin "6") (pinfunction "OUT1_6") (pintype "input"))
    )
    (net (code "21") (name "MOTOR2_2") (class "Default")
      (node (ref "H4") (pin "1") (pinfunction "1_1") (pintype "input"))
      (node (ref "U3") (pin "8") (pinfunction "OUT2_8") (pintype "input"))
    )
    (net (code "22") (name "MOTOR3_1") (class "Default")
      (node (ref "H5") (pin "6") (pinfunction "6_6") (pintype "input"))
      (node (ref "U4") (pin "6") (pinfunction "OUT1_6") (pintype "input"))
    )
    (net (code "23") (name "MOTOR3_2") (class "Default")
      (node (ref "H5") (pin "1") (pinfunction "1_1") (pintype "input"))
      (node (ref "U4") (pin "8") (pinfunction "OUT2_8") (pintype "input"))
    )
    (net (code "24") (name "MOTOR4_1") (class "Default")
      (node (ref "H6") (pin "6") (pinfunction "6_6") (pintype "input"))
      (node (ref "U5") (pin "6") (pinfunction "OUT1_6") (pintype "input"))
    )
    (net (code "25") (name "MOTOR4_2") (class "Default")
      (node (ref "H6") (pin "1") (pinfunction "1_1") (pintype "input"))
      (node (ref "U5") (pin "8") (pinfunction "OUT2_8") (pintype "input"))
    )
    (net (code "26") (name "MOTOR_POWER") (class "Default")
      (node (ref "C1") (pin "2") (pinfunction "2_2") (pintype "input"))
      (node (ref "C2") (pin "1") (pinfunction "1_1") (pintype "input"))
      (node (ref "C3") (pin "2") (pinfunction "2_2") (pintype "input"))
      (node (ref "C4") (pin "1") (pinfunction "1_1") (pintype "input"))
      (node (ref "C5") (pin "2") (pinfunction "2_2") (pintype "input"))
      (node (ref "C6") (pin "1") (pinfunction "1_1") (pintype "input"))
      (node (ref "C7") (pin "2") (pinfunction "2_2") (pintype "input"))
      (node (ref "C8") (pin "1") (pinfunction "1_1") (pintype "input"))
      (node (ref "D2") (pin "2") (pinfunction "2_2") (pintype "input"))
      (node (ref "R20") (pin "2") (pinfunction "2_2") (pintype "input"))
      (node (ref "U10") (pin "1") (pinfunction "1_1") (pintype "input"))
      (node (ref "U2") (pin "5") (pinfunction "VM_5") (pintype "input"))
      (node (ref "U3") (pin "5") (pinfunction "VM_5") (pintype "input"))
      (node (ref "U4") (pin "5") (pinfunction "VM_5") (pintype "input"))
      (node (ref "U5") (pin "5") (pinfunction "VM_5") (pintype "input"))
    )
    (net (code "27") (name "NRST") (class "Default")
      (node (ref "C13") (pin "1") (pinfunction "1_1") (pintype "input"))
      (node (ref "KEY1") (pin "1") (pinfunction "1_1") (pintype "input"))
      (node (ref "R14") (pin "1") (pinfunction "1_1") (pintype "input"))
      (node (ref "U1") (pin "7") (pinfunction "NRST_7") (pintype "input"))
    )
    (net (code "28") (name "Net-(H8-Pad10)") (class "Default")
      (node (ref "H8") (pin "10") (pinfunction "10_10") (pintype "input"))
      (node (ref "R24") (pin "2") (pinfunction "2_2") (pintype "input"))
    )
    (net (code "29") (name "Net-(LED1-A)") (class "Default")
      (node (ref "LED1") (pin "2") (pinfunction "A_2") (pintype "input"))
      (node (ref "R18") (pin "1") (pinfunction "1_1") (pintype "input"))
    )
    (net (code "30") (name "Net-(LED2-A)") (class "Default")
      (node (ref "LED2") (pin "2") (pinfunction "A_2") (pintype "input"))
      (node (ref "R20") (pin "1") (pinfunction "1_1") (pintype "input"))
    )
    (net (code "31") (name "Net-(U1-VBAT)") (class "Default")
      (node (ref "R15") (pin "1") (pinfunction "1_1") (pintype "input"))
      (node (ref "U1") (pin "1") (pinfunction "VBAT_1") (pintype "input"))
    )
    (net (code "32") (name "Net-(U2-ISEN)") (class "Default")
      (node (ref "R3") (pin "2") (pinfunction "2_2") (pintype "input"))
      (node (ref "U2") (pin "7") (pinfunction "ISEN_7") (pintype "input"))
    )
    (net (code "33") (name "Net-(U2-VERF)") (class "Default")
      (node (ref "R1") (pin "2") (pinfunction "2_2") (pintype "input"))
      (node (ref "R2") (pin "2") (pinfunction "2_2") (pintype "input"))
      (node (ref "U2") (pin "4") (pinfunction "VERF_4") (pintype "input"))
    )
    (net (code "34") (name "Net-(U3-ISEN)") (class "Default")
      (node (ref "R6") (pin "2") (pinfunction "2_2") (pintype "input"))
      (node (ref "U3") (pin "7") (pinfunction "ISEN_7") (pintype "input"))
    )
    (net (code "35") (name "Net-(U3-VERF)") (class "Default")
      (node (ref "R4") (pin "2") (pinfunction "2_2") (pintype "input"))
      (node (ref "R5") (pin "2") (pinfunction "2_2") (pintype "input"))
      (node (ref "U3") (pin "4") (pinfunction "VERF_4") (pintype "input"))
    )
    (net (code "36") (name "Net-(U4-ISEN)") (class "Default")
      (node (ref "R9") (pin "2") (pinfunction "2_2") (pintype "input"))
      (node (ref "U4") (pin "7") (pinfunction "ISEN_7") (pintype "input"))
    )
    (net (code "37") (name "Net-(U4-VERF)") (class "Default")
      (node (ref "R7") (pin "2") (pinfunction "2_2") (pintype "input"))
      (node (ref "R8") (pin "2") (pinfunction "2_2") (pintype "input"))
      (node (ref "U4") (pin "4") (pinfunction "VERF_4") (pintype "input"))
    )
    (net (code "38") (name "Net-(U5-ISEN)") (class "Default")
      (node (ref "R12") (pin "2") (pinfunction "2_2") (pintype "input"))
      (node (ref "U5") (pin "7") (pinfunction "ISEN_7") (pintype "input"))
    )
    (net (code "39") (name "Net-(U5-VERF)") (class "Default")
      (node (ref "R10") (pin "2") (pinfunction "2_2") (pintype "input"))
      (node (ref "R11") (pin "2") (pinfunction "2_2") (pintype "input"))
      (node (ref "U5") (pin "4") (pinfunction "VERF_4") (pintype "input"))
    )
    (net (code "40") (name "Net-(U7-OUTPUT)") (class "Default")
      (node (ref "D1") (pin "1") (pinfunction "1_1") (pintype "input"))
      (node (ref "L2") (pin "2") (pinfunction "2_2") (pintype "input"))
      (node (ref "U7") (pin "2") (pinfunction "OUTPUT_2") (pintype "input"))
    )
    (net (code "41") (name "OSC32_IN") (class "Default")
      (node (ref "C12") (pin "1") (pinfunction "1_1") (pintype "input"))
      (node (ref "U1") (pin "3") (pinfunction "PC14-OSC32_IN_3") (pintype "input"))
      (node (ref "X3") (pin "2") (pinfunction "2_2") (pintype "input"))
    )
    (net (code "42") (name "OSC32_OUT") (class "Default")
      (node (ref "C11") (pin "2") (pinfunction "2_2") (pintype "input"))
      (node (ref "U1") (pin "4") (pinfunction "PC15-OSC32_OUT_4") (pintype "input"))
      (node (ref "X3") (pin "1") (pinfunction "1_1") (pintype "input"))
    )
    (net (code "43") (name "OSC_IN") (class "Default")
      (node (ref "C9") (pin "2") (pinfunction "2_2") (pintype "input"))
      (node (ref "R13") (pin "2") (pinfunction "2_2") (pintype "input"))
      (node (ref "U1") (pin "5") (pinfunction "PDO-OSC_IN_5") (pintype "input"))
      (node (ref "X2") (pin "3") (pinfunction "3_3") (pintype "input"))
    )
    (net (code "44") (name "OSC_OUT") (class "Default")
      (node (ref "C10") (pin "2") (pinfunction "2_2") (pintype "input"))
      (node (ref "R13") (pin "1") (pinfunction "1_1") (pintype "input"))
      (node (ref "U1") (pin "6") (pinfunction "PD1-OSC_OUT_6") (pintype "input"))
      (node (ref "X2") (pin "1") (pinfunction "1_1") (pintype "input"))
    )
    (net (code "45") (name "POWER") (class "Default")
      (node (ref "CN2") (pin "1") (pinfunction "+_1") (pintype "input"))
      (node (ref "CN3") (pin "1") (pinfunction "1_1") (pintype "input"))
      (node (ref "U10") (pin "2") (pinfunction "2_2") (pintype "input"))
      (node (ref "U11") (pin "1") (pinfunction "1_1") (pintype "input"))
    )
    (net (code "46") (name "PWM1_1") (class "Default")
      (node (ref "U1") (pin "37") (pinfunction "PC6_37") (pintype "input"))
      (node (ref "U2") (pin "3") (pinfunction "IN1_3") (pintype "input"))
    )
    (net (code "47") (name "PWM1_2") (class "Default")
      (node (ref "U1") (pin "38") (pinfunction "PC7_38") (pintype "input"))
      (node (ref "U2") (pin "2") (pinfunction "IN2_2") (pintype "input"))
    )
    (net (code "48") (name "PWM2_1") (class "Default")
      (node (ref "U1") (pin "39") (pinfunction "PC8_39") (pintype "input"))
      (node (ref "U3") (pin "3") (pinfunction "IN1_3") (pintype "input"))
    )
    (net (code "49") (name "PWM2_2") (class "Default")
      (node (ref "U1") (pin "40") (pinfunction "PC9_40") (pintype "input"))
      (node (ref "U3") (pin "2") (pinfunction "IN2_2") (pintype "input"))
    )
    (net (code "50") (name "PWM3_1") (class "Default")
      (node (ref "U1") (pin "41") (pinfunction "PA8_41") (pintype "input"))
      (node (ref "U4") (pin "3") (pinfunction "IN1_3") (pintype "input"))
    )
    (net (code "51") (name "PWM3_2") (class "Default")
      (node (ref "U1") (pin "42") (pinfunction "PA9_42") (pintype "input"))
      (node (ref "U4") (pin "2") (pinfunction "IN2_2") (pintype "input"))
    )
    (net (code "52") (name "PWM4_1") (class "Default")
      (node (ref "U1") (pin "43") (pinfunction "PA10_43") (pintype "input"))
      (node (ref "U5") (pin "3") (pinfunction "IN1_3") (pintype "input"))
    )
    (net (code "53") (name "PWM4_2") (class "Default")
      (node (ref "U1") (pin "44") (pinfunction "PA11_44") (pintype "input"))
      (node (ref "U5") (pin "2") (pinfunction "IN2_2") (pintype "input"))
    )
    (net (code "54") (name "SPI1_BLK") (class "Default")
      (node (ref "H7") (pin "8") (pinfunction "8_8") (pintype "input"))
      (node (ref "U1") (pin "26") (pinfunction "PB0_26") (pintype "input"))
    )
    (net (code "55") (name "SPI1_CLK") (class "Default")
      (node (ref "H7") (pin "3") (pinfunction "3_3") (pintype "input"))
      (node (ref "U1") (pin "21") (pinfunction "PA5_21") (pintype "input"))
    )
    (net (code "56") (name "SPI1_CS") (class "Default")
      (node (ref "H7") (pin "7") (pinfunction "7_7") (pintype "input"))
      (node (ref "U1") (pin "25") (pinfunction "PC5_25") (pintype "input"))
    )
    (net (code "57") (name "SPI1_DC") (class "Default")
      (node (ref "H7") (pin "6") (pinfunction "6_6") (pintype "input"))
      (node (ref "U1") (pin "24") (pinfunction "PC4_24") (pintype "input"))
    )
    (net (code "58") (name "SPI1_MISO") (class "Default")
      (node (ref "U1") (pin "22") (pinfunction "PA6_22") (pintype "input"))
    )
    (net (code "59") (name "SPI1_MOSI") (class "Default")
      (node (ref "H7") (pin "4") (pinfunction "4_4") (pintype "input"))
      (node (ref "U1") (pin "23") (pinfunction "PA7_23") (pintype "input"))
    )
    (net (code "60") (name "SPI1_RST") (class "Default")
      (node (ref "H7") (pin "5") (pinfunction "5_5") (pintype "input"))
      (node (ref "U1") (pin "20") (pinfunction "PA4_20") (pintype "input"))
    )
    (net (code "61") (name "SWCLK") (class "Default")
      (node (ref "H2") (pin "4") (pinfunction "4_4") (pintype "input"))
      (node (ref "R16") (pin "2") (pinfunction "2_2") (pintype "input"))
      (node (ref "U1") (pin "49") (pinfunction "PA14_49") (pintype "input"))
    )
    (net (code "62") (name "SWDIO") (class "Default")
      (node (ref "H2") (pin "3") (pinfunction "3_3") (pintype "input"))
      (node (ref "R17") (pin "1") (pinfunction "1_1") (pintype "input"))
      (node (ref "U1") (pin "46") (pinfunction "PA13_46") (pintype "input"))
    )
    (net (code "63") (name "SW_1") (class "Default")
      (node (ref "R21") (pin "2") (pinfunction "2_2") (pintype "input"))
      (node (ref "SW2") (pin "6") (pinfunction "PIN6_6") (pintype "input"))
      (node (ref "U1") (pin "8") (pinfunction "PC0_8") (pintype "input"))
    )
    (net (code "64") (name "SW_2") (class "Default")
      (node (ref "R22") (pin "2") (pinfunction "2_2") (pintype "input"))
      (node (ref "SW2") (pin "5") (pinfunction "PIN5_5") (pintype "input"))
      (node (ref "U1") (pin "9") (pinfunction "PC1_9") (pintype "input"))
    )
    (net (code "65") (name "SW_3") (class "Default")
      (node (ref "R23") (pin "2") (pinfunction "2_2") (pintype "input"))
      (node (ref "SW2") (pin "4") (pinfunction "PIN4_4") (pintype "input"))
      (node (ref "U1") (pin "10") (pinfunction "PC2_10") (pintype "input"))
    )
    (net (code "66") (name "TIM2_CH1") (class "Default")
      (node (ref "H4") (pin "3") (pinfunction "3_3") (pintype "input"))
      (node (ref "U1") (pin "50") (pinfunction "PA15_50") (pintype "input"))
    )
    (net (code "67") (name "TIM2_CH2") (class "Default")
      (node (ref "H4") (pin "4") (pinfunction "4_4") (pintype "input"))
      (node (ref "U1") (pin "55") (pinfunction "PB3_55") (pintype "input"))
    )
    (net (code "68") (name "TIM3_CH1") (class "Default")
      (node (ref "H3") (pin "3") (pinfunction "3_3") (pintype "input"))
      (node (ref "U1") (pin "56") (pinfunction "PB4_56") (pintype "input"))
    )
    (net (code "69") (name "TIM3_CH2") (class "Default")
      (node (ref "H3") (pin "4") (pinfunction "4_4") (pintype "input"))
      (node (ref "U1") (pin "57") (pinfunction "PB5_57") (pintype "input"))
    )
    (net (code "70") (name "TIM4_CH1") (class "Default")
      (node (ref "H5") (pin "3") (pinfunction "3_3") (pintype "input"))
      (node (ref "U1") (pin "58") (pinfunction "PB6_58") (pintype "input"))
    )
    (net (code "71") (name "TIM4_CH2") (class "Default")
      (node (ref "H5") (pin "4") (pinfunction "4_4") (pintype "input"))
      (node (ref "U1") (pin "59") (pinfunction "PB7_59") (pintype "input"))
    )
    (net (code "72") (name "TIM5_CH1") (class "Default")
      (node (ref "H6") (pin "3") (pinfunction "3_3") (pintype "input"))
      (node (ref "U1") (pin "14") (pinfunction "PA0-WKUP_14") (pintype "input"))
    )
    (net (code "73") (name "TIM5_CH2") (class "Default")
      (node (ref "H6") (pin "4") (pinfunction "4_4") (pintype "input"))
      (node (ref "U1") (pin "15") (pinfunction "PA1_15") (pintype "input"))
    )
    (net (code "74") (name "USART2_RX") (class "Default")
      (node (ref "CN4") (pin "4") (pinfunction "4_4") (pintype "input"))
      (node (ref "U1") (pin "17") (pinfunction "PA3_17") (pintype "input"))
    )
    (net (code "75") (name "USART2_TX") (class "Default")
      (node (ref "CN4") (pin "3") (pinfunction "3_3") (pintype "input"))
      (node (ref "U1") (pin "16") (pinfunction "PA2_16") (pintype "input"))
    )
    (net (code "76") (name "VCC") (class "Default")
      (node (ref "C14") (pin "2") (pinfunction "2_2") (pintype "input"))
      (node (ref "C15") (pin "2") (pinfunction "2_2") (pintype "input"))
      (node (ref "C16") (pin "2") (pinfunction "2_2") (pintype "input"))
      (node (ref "C17") (pin "2") (pinfunction "2_2") (pintype "input"))
      (node (ref "C18") (pin "2") (pinfunction "2_2") (pintype "input"))
      (node (ref "C24") (pin "2") (pinfunction "2_2") (pintype "input"))
      (node (ref "CN4") (pin "1") (pinfunction "1_1") (pintype "input"))
      (node (ref "H1") (pin "1") (pinfunction "1_1") (pintype "input"))
      (node (ref "H1") (pin "2") (pinfunction "2_2") (pintype "input"))
      (node (ref "H2") (pin "1") (pinfunction "1_1") (pintype "input"))
      (node (ref "H7") (pin "2") (pinfunction "2_2") (pintype "input"))
      (node (ref "H8") (pin "1") (pinfunction "1_1") (pintype "input"))
      (node (ref "R11") (pin "1") (pinfunction "1_1") (pintype "input"))
      (node (ref "R14") (pin "2") (pinfunction "2_2") (pintype "input"))
      (node (ref "R15") (pin "2") (pinfunction "2_2") (pintype "input"))
      (node (ref "R17") (pin "2") (pinfunction "2_2") (pintype "input"))
      (node (ref "R18") (pin "2") (pinfunction "2_2") (pintype "input"))
      (node (ref "R2") (pin "1") (pinfunction "1_1") (pintype "input"))
      (node (ref "R21") (pin "1") (pinfunction "1_1") (pintype "input"))
      (node (ref "R22") (pin "1") (pinfunction "1_1") (pintype "input"))
      (node (ref "R23") (pin "1") (pinfunction "1_1") (pintype "input"))
      (node (ref "R5") (pin "1") (pinfunction "1_1") (pintype "input"))
      (node (ref "R8") (pin "1") (pinfunction "1_1") (pintype "input"))
      (node (ref "U1") (pin "13") (pinfunction "VDDA_13") (pintype "input"))
      (node (ref "U1") (pin "19") (pinfunction "VDD_4_19") (pintype "input"))
      (node (ref "U1") (pin "32") (pinfunction "VDD_1_32") (pintype "input"))
      (node (ref "U1") (pin "48") (pinfunction "VDD_2_48") (pintype "input"))
      (node (ref "U1") (pin "64") (pinfunction "VDD_3_64") (pintype "input"))
      (node (ref "U8") (pin "2") (pinfunction "VOUT_2") (pintype "input"))
      (node (ref "U8") (pin "4") (pinfunction "VOUT_4") (pintype "input"))
    )
    (net (code "77") (name "unconnected-(CN1-Pad5)") (class "Default")
      (node (ref "CN1") (pin "5") (pinfunction "5_5") (pintype "input"))
    )
    (net (code "78") (name "unconnected-(CN1-Pad6)") (class "Default")
      (node (ref "CN1") (pin "6") (pinfunction "6_6") (pintype "input"))
    )
    (net (code "79") (name "unconnected-(CN4-Pad5)") (class "Default")
      (node (ref "CN4") (pin "5") (pinfunction "5_5") (pintype "input"))
    )
    (net (code "80") (name "unconnected-(CN4-Pad6)") (class "Default")
      (node (ref "CN4") (pin "6") (pinfunction "6_6") (pintype "input"))
    )
    (net (code "81") (name "unconnected-(H8-Pad5)") (class "Default")
      (node (ref "H8") (pin "5") (pinfunction "5_5") (pintype "input+no_connect"))
    )
    (net (code "82") (name "unconnected-(H8-Pad6)") (class "Default")
      (node (ref "H8") (pin "6") (pinfunction "6_6") (pintype "input+no_connect"))
    )
    (net (code "83") (name "unconnected-(H8-Pad7)") (class "Default")
      (node (ref "H8") (pin "7") (pinfunction "7_7") (pintype "input+no_connect"))
    )
    (net (code "84") (name "unconnected-(H8-Pad8)") (class "Default")
      (node (ref "H8") (pin "8") (pinfunction "8_8") (pintype "input+no_connect"))
    )
    (net (code "85") (name "unconnected-(H8-Pad9)") (class "Default")
      (node (ref "H8") (pin "9") (pinfunction "9_9") (pintype "input+no_connect"))
    )
    (net (code "86") (name "unconnected-(U1-PA12-Pad45)") (class "Default")
      (node (ref "U1") (pin "45") (pinfunction "PA12_45") (pintype "input"))
    )
    (net (code "87") (name "unconnected-(U1-PB1-Pad27)") (class "Default")
      (node (ref "U1") (pin "27") (pinfunction "PB1_27") (pintype "input"))
    )
    (net (code "88") (name "unconnected-(U1-PB13-Pad34)") (class "Default")
      (node (ref "U1") (pin "34") (pinfunction "PB13_34") (pintype "input"))
    )
    (net (code "89") (name "unconnected-(U1-PB14-Pad35)") (class "Default")
      (node (ref "U1") (pin "35") (pinfunction "PB14_35") (pintype "input"))
    )
    (net (code "90") (name "unconnected-(U1-PB15-Pad36)") (class "Default")
      (node (ref "U1") (pin "36") (pinfunction "PB15_36") (pintype "input"))
    )
    (net (code "91") (name "unconnected-(U1-PC3-Pad11)") (class "Default")
      (node (ref "U1") (pin "11") (pinfunction "PC3_11") (pintype "input"))
    )
    (net (code "92") (name "unconnected-(U9-VREF-Pad5)") (class "Default")
      (node (ref "U9") (pin "5") (pinfunction "VREF_5") (pintype "input"))
    )
    (net (code "93") (name "unconnected-(U10-Pad3)") (class "Default")
      (node (ref "U10") (pin "3") (pinfunction "3_3") (pintype "input"))
    )
    (net (code "94") (name "unconnected-(U10-Pad4)") (class "Default")
      (node (ref "U10") (pin "4") (pinfunction "4_4") (pintype "input"))
    )
    (net (code "95") (name "unconnected-(U10-Pad5)") (class "Default")
      (node (ref "U10") (pin "5") (pinfunction "5_5") (pintype "input"))
    )
    (net (code "96") (name "unconnected-(X2-Pad2)") (class "Default")
      (node (ref "X2") (pin "2") (pinfunction "2_2") (pintype "input"))
    )
    (net (code "97") (name "unconnected-(X2-Pad4)") (class "Default")
      (node (ref "X2") (pin "4") (pinfunction "4_4") (pintype "input"))
    )
  )
)
